# 5-MCU.net
KiCad netlist of a schematic drawn in Altium Designer
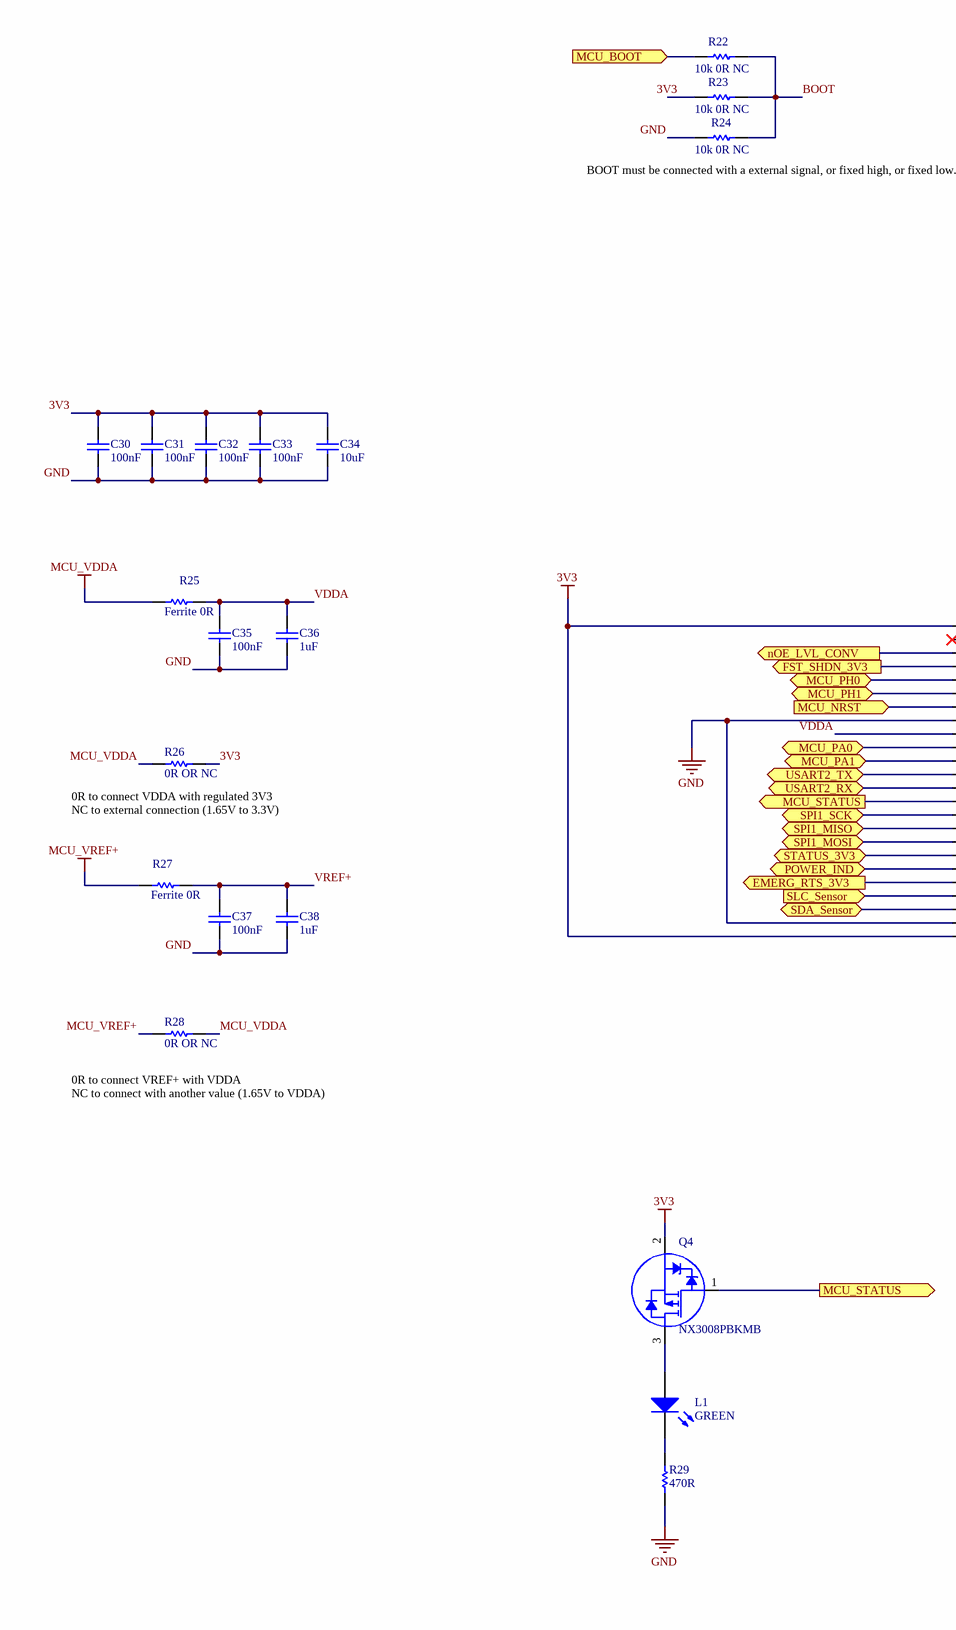
[diagram p0: 5-MCU.SchDoc, left]
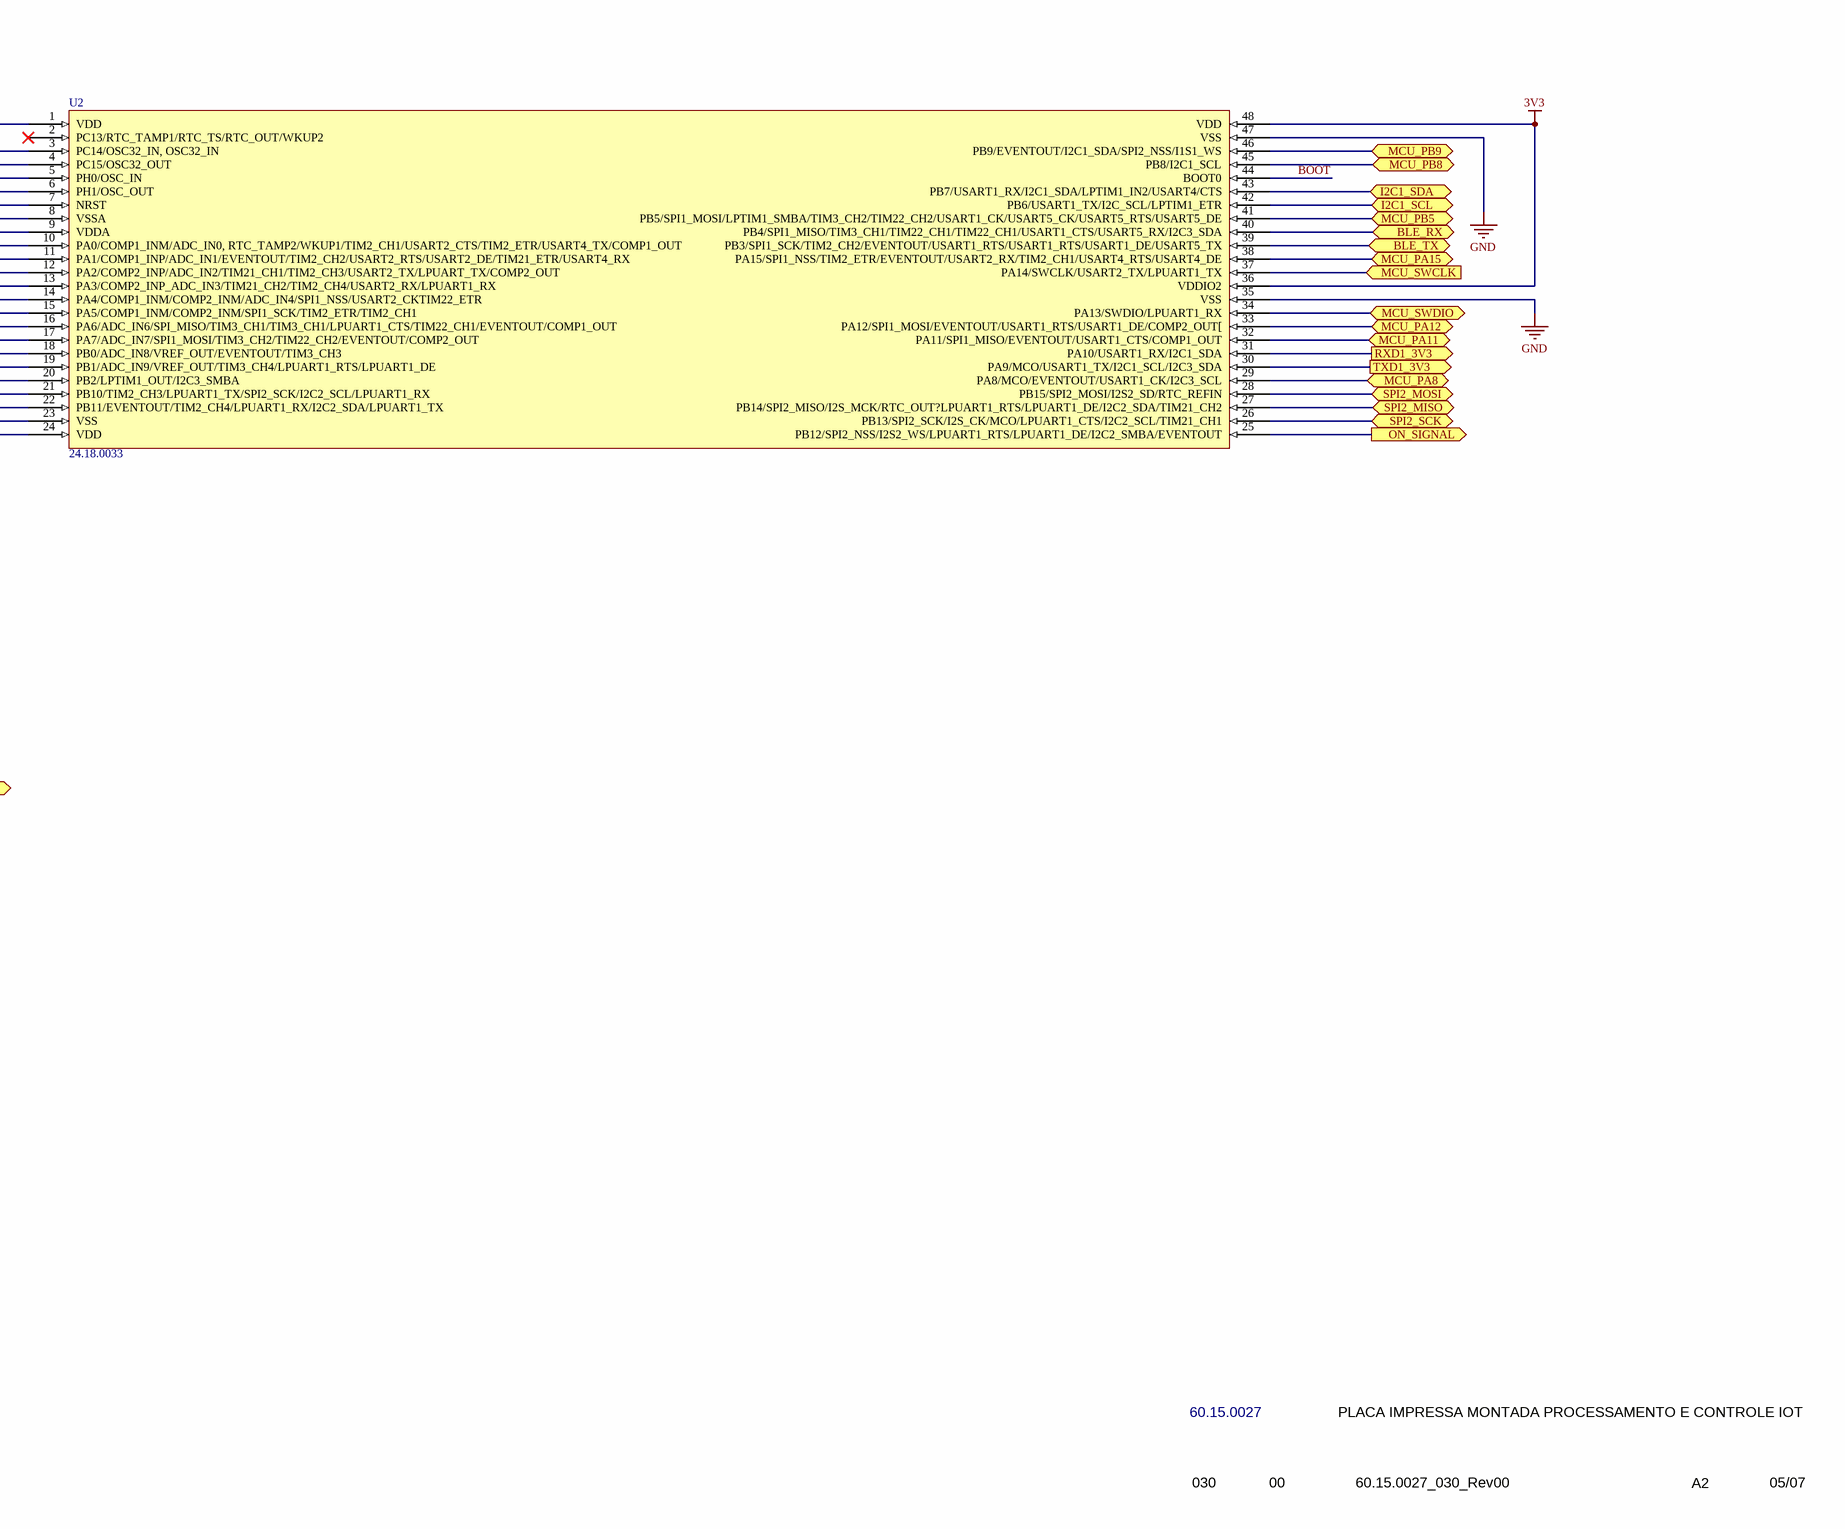
[diagram p1: 5-MCU.SchDoc, right]

(export (version "E")
  (design (tool "Eeschema 10.0.6"))
  (components
    (comp (ref "C30")
      (value "16.23.0803")
      (footprint "16.23.0803")
      (description "CAPACITOR CERAMICO 100nF 16V 10%% X5R SMD 0201")
      (fields (field (name "ALTIUM_UNNAMED_1") "100nF"))
      (libsource (lib "OMNI-CAPACITORES") (part "16.23.0803"))
    )
    (comp (ref "C31")
      (value "16.23.0803")
      (footprint "16.23.0803")
      (description "CAPACITOR CERAMICO 100nF 16V 10%% X5R SMD 0201")
      (fields (field (name "ALTIUM_UNNAMED_1") "100nF"))
      (libsource (lib "OMNI-CAPACITORES") (part "16.23.0803"))
    )
    (comp (ref "C32")
      (value "16.23.0803")
      (footprint "16.23.0803")
      (description "CAPACITOR CERAMICO 100nF 16V 10%% X5R SMD 0201")
      (fields (field (name "ALTIUM_UNNAMED_1") "100nF"))
      (libsource (lib "OMNI-CAPACITORES") (part "16.23.0803"))
    )
    (comp (ref "C33")
      (value "16.23.0803")
      (footprint "16.23.0803")
      (description "CAPACITOR CERAMICO 100nF 16V 10%% X5R SMD 0201")
      (fields (field (name "ALTIUM_UNNAMED_1") "100nF"))
      (libsource (lib "OMNI-CAPACITORES") (part "16.23.0803"))
    )
    (comp (ref "C34")
      (value "10uF")
      (footprint "16.23.0805")
      (description "CAPACITOR CERAMICO MULTICAMADAS 10uF 10V X5R 10% SMD 0603")
      (fields (field (name "Comment") "16.23.0805"))
      (libsource (lib "OMNI-CAPACITORES") (part "16.23.0805"))
    )
    (comp (ref "C35")
      (value "16.23.0803")
      (footprint "16.23.0803")
      (description "CAPACITOR CERAMICO 100nF 16V 10%% X5R SMD 0201")
      (fields (field (name "ALTIUM_UNNAMED_1") "100nF"))
      (libsource (lib "OMNI-CAPACITORES") (part "16.23.0803"))
    )
    (comp (ref "C36")
      (value "1uF")
      (footprint "16.23.0806")
      (description "CAPACITOR CERAMICO MULTICAMADAS 1uF 10V X5R 20% SMD 0201")
      (fields (field (name "Comment") "16.23.0806"))
      (libsource (lib "OMNI-CAPACITORES") (part "16.23.0806"))
    )
    (comp (ref "C37")
      (value "16.23.0803")
      (footprint "16.23.0803")
      (description "CAPACITOR CERAMICO 100nF 16V 10%% X5R SMD 0201")
      (fields (field (name "ALTIUM_UNNAMED_1") "100nF"))
      (libsource (lib "OMNI-CAPACITORES") (part "16.23.0803"))
    )
    (comp (ref "C38")
      (value "1uF")
      (footprint "16.23.0806")
      (description "CAPACITOR CERAMICO MULTICAMADAS 1uF 10V X5R 20% SMD 0201")
      (fields (field (name "Comment") "16.23.0806"))
      (libsource (lib "OMNI-CAPACITORES") (part "16.23.0806"))
    )
    (comp (ref "L1")
      (value "32.17.0036")
      (footprint "32.17.0036")
      (description "LED VERDE 0603 SMD")
      (fields (field (name "ALTIUM_UNNAMED_1") "GREEN"))
      (libsource (lib "OMNI-DIODOS_LED´s_DISPLAYS") (part "32.17.0036"))
    )
    (comp (ref "Q4")
      (value "72.19.0071")
      (footprint "72.19.0071")
      (description "MOSFET CANAL P SMD 30V 230mA SOT883B")
      (fields (field (name "ALTIUM_UNNAMED_1") "NX3008PBKMB"))
      (libsource (lib "OMNI-TRANSISTORES") (part "72.19.0071"))
    )
    (comp (ref "R22")
      (value "10k 0R NC")
      (footprint "66.21.1646")
      (description "RESISTOR THICK FILM 10k OHMS 25V 0.05W 1% SMD 0201")
      (fields (field (name "Comment") "66.21.1646"))
      (libsource (lib "OMNI-RESISTORES") (part "66.21.1646"))
    )
    (comp (ref "R23")
      (value "10k 0R NC")
      (footprint "66.21.1646")
      (description "RESISTOR THICK FILM 10k OHMS 25V 0.05W 1% SMD 0201")
      (fields (field (name "Comment") "66.21.1646"))
      (libsource (lib "OMNI-RESISTORES") (part "66.21.1646"))
    )
    (comp (ref "R24")
      (value "10k 0R NC")
      (footprint "66.21.1646")
      (description "RESISTOR THICK FILM 10k OHMS 25V 0.05W 1% SMD 0201")
      (fields (field (name "Comment") "66.21.1646"))
      (libsource (lib "OMNI-RESISTORES") (part "66.21.1646"))
    )
    (comp (ref "R25")
      (value "Ferrite 0R")
      (footprint "66.24.1337")
      (description "RESISTOR THICK FILM 0,1W 0 OHMS SMD 0603")
      (fields (field (name "Comment") "66.24.1337"))
      (libsource (lib "OMNI-RESISTORES") (part "66.24.1337"))
    )
    (comp (ref "R26")
      (value "0R OR NC")
      (footprint "66.24.1337")
      (description "RESISTOR THICK FILM 0,1W 0 OHMS SMD 0603")
      (fields (field (name "Comment") "66.24.1337"))
      (libsource (lib "OMNI-RESISTORES") (part "66.24.1337"))
    )
    (comp (ref "R27")
      (value "Ferrite 0R")
      (footprint "66.24.1337")
      (description "RESISTOR THICK FILM 0,1W 0 OHMS SMD 0603")
      (fields (field (name "Comment") "66.24.1337"))
      (libsource (lib "OMNI-RESISTORES") (part "66.24.1337"))
    )
    (comp (ref "R28")
      (value "0R OR NC")
      (footprint "66.24.1337")
      (description "RESISTOR THICK FILM 0,1W 0 OHMS SMD 0603")
      (fields (field (name "Comment") "66.24.1337"))
      (libsource (lib "OMNI-RESISTORES") (part "66.24.1337"))
    )
    (comp (ref "R29")
      (value "470R")
      (footprint "66.33.4700")
      (description "RES MET 0,125W 470 OHMS 5% SMD 0805")
      (fields (field (name "Comment") "66.33.4700"))
      (libsource (lib "OMNI-RESISTORES") (part "66.33.4700"))
    )
    (comp (ref "U2")
      (value "24.18.0033")
      (footprint "24.18.0033")
      (description "MICROCONTROLADOR 32BITS ARM 192KB FLASH 48 PINOS LQFP")
      (fields (field (name "PART NUMBER") "STM32L071CZTx"))
      (libsource (lib "OMNI-CI´S DIGITAIS") (part "24.18.0033"))
    )
  )
  (nets
    (net (code "1") (name "/BLE_RX") (class "Default")
      (node (ref "U2") (pin "40") (pinfunction "PB4/SPI1_MISO/TIM3_CH1/TIM22_CH1/TIM22_CH1/USART1_CTS/USART5_RX/I2C3_SDA_40") (pintype "input"))
    )
    (net (code "2") (name "/BLE_TX") (class "Default")
      (node (ref "U2") (pin "39") (pinfunction "PB3/SPI1_SCK/TIM2_CH2/EVENTOUT/USART1_RTS/USART1_RTS/USART1_DE/USART5_TX_39") (pintype "input"))
    )
    (net (code "3") (name "/BOOT") (class "Default")
      (node (ref "R22") (pin "2") (pinfunction "2_2") (pintype "passive"))
      (node (ref "R23") (pin "2") (pinfunction "2_2") (pintype "passive"))
      (node (ref "R24") (pin "2") (pinfunction "2_2") (pintype "passive"))
      (node (ref "U2") (pin "44") (pinfunction "BOOT0_44") (pintype "input"))
    )
    (net (code "4") (name "/EMERG_RTS_3V3") (class "Default")
      (node (ref "U2") (pin "20") (pinfunction "PB2/LPTIM1_OUT/I2C3_SMBA_20") (pintype "input"))
    )
    (net (code "5") (name "/FST_SHDN_3V3") (class "Default")
      (node (ref "U2") (pin "4") (pinfunction "PC15/OSC32_OUT_4") (pintype "input"))
    )
    (net (code "6") (name "/I2C1_SCL") (class "Default")
      (node (ref "U2") (pin "42") (pinfunction "PB6/USART1_TX/I2C_SCL/LPTIM1_ETR_42") (pintype "input"))
    )
    (net (code "7") (name "/I2C1_SDA") (class "Default")
      (node (ref "U2") (pin "43") (pinfunction "PB7/USART1_RX/I2C1_SDA/LPTIM1_IN2/USART4/CTS_43") (pintype "input"))
    )
    (net (code "8") (name "/MCU_BOOT") (class "Default")
      (node (ref "R22") (pin "1") (pinfunction "1_1") (pintype "passive"))
    )
    (net (code "9") (name "/MCU_NRST") (class "Default")
      (node (ref "U2") (pin "7") (pinfunction "NRST_7") (pintype "input"))
    )
    (net (code "10") (name "/MCU_PA0") (class "Default")
      (node (ref "U2") (pin "10") (pinfunction "PA0/COMP1_INM/ADC_IN0,_RTC_TAMP2/WKUP1/TIM2_CH1/USART2_CTS/TIM2_ETR/USART4_TX/COMP1_OUT_10") (pintype "input"))
    )
    (net (code "11") (name "/MCU_PA1") (class "Default")
      (node (ref "U2") (pin "11") (pinfunction "PA1/COMP1_INP/ADC_IN1/EVENTOUT/TIM2_CH2/USART2_RTS/USART2_DE/TIM21_ETR/USART4_RX_11") (pintype "input"))
    )
    (net (code "12") (name "/MCU_PA8") (class "Default")
      (node (ref "U2") (pin "29") (pinfunction "PA8/MCO/EVENTOUT/USART1_CK/I2C3_SCL_29") (pintype "input"))
    )
    (net (code "13") (name "/MCU_PA11") (class "Default")
      (node (ref "U2") (pin "32") (pinfunction "PA11/SPI1_MISO/EVENTOUT/USART1_CTS/COMP1_OUT_32") (pintype "input"))
    )
    (net (code "14") (name "/MCU_PA12") (class "Default")
      (node (ref "U2") (pin "33") (pinfunction "PA12/SPI1_MOSI/EVENTOUT/USART1_RTS/USART1_DE/COMP2_OUT[_33") (pintype "input"))
    )
    (net (code "15") (name "/MCU_PA15") (class "Default")
      (node (ref "U2") (pin "38") (pinfunction "PA15/SPI1_NSS/TIM2_ETR/EVENTOUT/USART2_RX/TIM2_CH1/USART4_RTS/USART4_DE_38") (pintype "input"))
    )
    (net (code "16") (name "/MCU_PB5") (class "Default")
      (node (ref "U2") (pin "41") (pinfunction "PB5/SPI1_MOSI/LPTIM1_SMBA/TIM3_CH2/TIM22_CH2/USART1_CK/USART5_CK/USART5_RTS/USART5_DE_41") (pintype "input"))
    )
    (net (code "17") (name "/MCU_PB8") (class "Default")
      (node (ref "U2") (pin "45") (pinfunction "PB8/I2C1_SCL_45") (pintype "input"))
    )
    (net (code "18") (name "/MCU_PB9") (class "Default")
      (node (ref "U2") (pin "46") (pinfunction "PB9/EVENTOUT/I2C1_SDA/SPI2_NSS/I1S1_WS_46") (pintype "input"))
    )
    (net (code "19") (name "/MCU_PH0") (class "Default")
      (node (ref "U2") (pin "5") (pinfunction "PH0/OSC_IN_5") (pintype "input"))
    )
    (net (code "20") (name "/MCU_PH1") (class "Default")
      (node (ref "U2") (pin "6") (pinfunction "PH1/OSC_OUT_6") (pintype "input"))
    )
    (net (code "21") (name "/MCU_STATUS") (class "Default")
      (node (ref "Q4") (pin "1") (pinfunction "G_1") (pintype "passive"))
      (node (ref "U2") (pin "14") (pinfunction "PA4/COMP1_INM/COMP2_INM/ADC_IN4/SPI1_NSS/USART2_CKTIM22_ETR_14") (pintype "input"))
    )
    (net (code "22") (name "/MCU_SWCLK") (class "Default")
      (node (ref "U2") (pin "37") (pinfunction "PA14/SWCLK/USART2_TX/LPUART1_TX_37") (pintype "input"))
    )
    (net (code "23") (name "/MCU_SWDIO") (class "Default")
      (node (ref "U2") (pin "34") (pinfunction "PA13/SWDIO/LPUART1_RX_34") (pintype "input"))
    )
    (net (code "24") (name "/ON_SIGNAL") (class "Default")
      (node (ref "U2") (pin "25") (pinfunction "PB12/SPI2_NSS/I2S2_WS/LPUART1_RTS/LPUART1_DE/I2C2_SMBA/EVENTOUT_25") (pintype "input"))
    )
    (net (code "25") (name "/POWER_IND") (class "Default")
      (node (ref "U2") (pin "19") (pinfunction "PB1/ADC_IN9/VREF_OUT/TIM3_CH4/LPUART1_RTS/LPUART1_DE_19") (pintype "input"))
    )
    (net (code "26") (name "/RXD1_3V3") (class "Default")
      (node (ref "U2") (pin "31") (pinfunction "PA10/USART1_RX/I2C1_SDA_31") (pintype "input"))
    )
    (net (code "27") (name "/SDA_Sensor") (class "Default")
      (node (ref "U2") (pin "22") (pinfunction "PB11/EVENTOUT/TIM2_CH4/LPUART1_RX/I2C2_SDA/LPUART1_TX_22") (pintype "input"))
    )
    (net (code "28") (name "/SLC_Sensor") (class "Default")
      (node (ref "U2") (pin "21") (pinfunction "PB10/TIM2_CH3/LPUART1_TX/SPI2_SCK/I2C2_SCL/LPUART1_RX_21") (pintype "input"))
    )
    (net (code "29") (name "/SPI1_MISO") (class "Default")
      (node (ref "U2") (pin "16") (pinfunction "PA6/ADC_IN6/SPI_MISO/TIM3_CH1/TIM3_CH1/LPUART1_CTS/TIM22_CH1/EVENTOUT/COMP1_OUT_16") (pintype "input"))
    )
    (net (code "30") (name "/SPI1_MOSI") (class "Default")
      (node (ref "U2") (pin "17") (pinfunction "PA7/ADC_IN7/SPI1_MOSI/TIM3_CH2/TIM22_CH2/EVENTOUT/COMP2_OUT_17") (pintype "input"))
    )
    (net (code "31") (name "/SPI1_SCK") (class "Default")
      (node (ref "U2") (pin "15") (pinfunction "PA5/COMP1_INM/COMP2_INM/SPI1_SCK/TIM2_ETR/TIM2_CH1_15") (pintype "input"))
    )
    (net (code "32") (name "/SPI2_MISO") (class "Default")
      (node (ref "U2") (pin "27") (pinfunction "PB14/SPI2_MISO/I2S_MCK/RTC_OUT?LPUART1_RTS/LPUART1_DE/I2C2_SDA/TIM21_CH2_27") (pintype "input"))
    )
    (net (code "33") (name "/SPI2_MOSI") (class "Default")
      (node (ref "U2") (pin "28") (pinfunction "PB15/SPI2_MOSI/I2S2_SD/RTC_REFIN_28") (pintype "input"))
    )
    (net (code "34") (name "/SPI2_SCK") (class "Default")
      (node (ref "U2") (pin "26") (pinfunction "PB13/SPI2_SCK/I2S_CK/MCO/LPUART1_CTS/I2C2_SCL/TIM21_CH1_26") (pintype "input"))
    )
    (net (code "35") (name "/STATUS_3V3") (class "Default")
      (node (ref "U2") (pin "18") (pinfunction "PB0/ADC_IN8/VREF_OUT/EVENTOUT/TIM3_CH3_18") (pintype "input"))
    )
    (net (code "36") (name "/TXD1_3V3") (class "Default")
      (node (ref "U2") (pin "30") (pinfunction "PA9/MCO/USART1_TX/I2C1_SCL/I2C3_SDA_30") (pintype "input"))
    )
    (net (code "37") (name "/USART2_RX") (class "Default")
      (node (ref "U2") (pin "13") (pinfunction "PA3/COMP2_INP_ADC_IN3/TIM21_CH2/TIM2_CH4/USART2_RX/LPUART1_RX_13") (pintype "input"))
    )
    (net (code "38") (name "/USART2_TX") (class "Default")
      (node (ref "U2") (pin "12") (pinfunction "PA2/COMP2_INP/ADC_IN2/TIM21_CH1/TIM2_CH3/USART2_TX/LPUART_TX/COMP2_OUT_12") (pintype "input"))
    )
    (net (code "39") (name "/VDDA") (class "Default")
      (node (ref "C35") (pin "2") (pinfunction "2_2") (pintype "passive"))
      (node (ref "C36") (pin "2") (pinfunction "2_2") (pintype "passive"))
      (node (ref "R25") (pin "2") (pinfunction "2_2") (pintype "passive"))
      (node (ref "U2") (pin "9") (pinfunction "VDDA_9") (pintype "input"))
    )
    (net (code "40") (name "/VREF+") (class "Default")
      (node (ref "C37") (pin "2") (pinfunction "2_2") (pintype "passive"))
      (node (ref "C38") (pin "2") (pinfunction "2_2") (pintype "passive"))
      (node (ref "R27") (pin "2") (pinfunction "2_2") (pintype "passive"))
    )
    (net (code "41") (name "/nOE_LVL_CONV") (class "Default")
      (node (ref "U2") (pin "3") (pinfunction "PC14/OSC32_IN,_OSC32_IN_3") (pintype "input"))
    )
    (net (code "42") (name "3V3") (class "Default")
      (node (ref "C30") (pin "2") (pinfunction "2_2") (pintype "passive"))
      (node (ref "C31") (pin "2") (pinfunction "2_2") (pintype "passive"))
      (node (ref "C32") (pin "2") (pinfunction "2_2") (pintype "passive"))
      (node (ref "C33") (pin "2") (pinfunction "2_2") (pintype "passive"))
      (node (ref "C34") (pin "2") (pinfunction "2_2") (pintype "passive"))
      (node (ref "Q4") (pin "2") (pinfunction "S_2") (pintype "passive"))
      (node (ref "R23") (pin "1") (pinfunction "1_1") (pintype "passive"))
      (node (ref "R26") (pin "2") (pinfunction "2_2") (pintype "passive"))
      (node (ref "U2") (pin "1") (pinfunction "VDD_1") (pintype "input"))
      (node (ref "U2") (pin "24") (pinfunction "VDD_24") (pintype "input"))
      (node (ref "U2") (pin "36") (pinfunction "VDDIO2_36") (pintype "input"))
      (node (ref "U2") (pin "48") (pinfunction "VDD_48") (pintype "input"))
    )
    (net (code "43") (name "GND") (class "Default")
      (node (ref "C30") (pin "1") (pinfunction "1_1") (pintype "passive"))
      (node (ref "C31") (pin "1") (pinfunction "1_1") (pintype "passive"))
      (node (ref "C32") (pin "1") (pinfunction "1_1") (pintype "passive"))
      (node (ref "C33") (pin "1") (pinfunction "1_1") (pintype "passive"))
      (node (ref "C34") (pin "1") (pinfunction "1_1") (pintype "passive"))
      (node (ref "C35") (pin "1") (pinfunction "1_1") (pintype "passive"))
      (node (ref "C36") (pin "1") (pinfunction "1_1") (pintype "passive"))
      (node (ref "C37") (pin "1") (pinfunction "1_1") (pintype "passive"))
      (node (ref "C38") (pin "1") (pinfunction "1_1") (pintype "passive"))
      (node (ref "R24") (pin "1") (pinfunction "1_1") (pintype "passive"))
      (node (ref "R29") (pin "1") (pinfunction "1_1") (pintype "passive"))
      (node (ref "U2") (pin "23") (pinfunction "VSS_23") (pintype "input"))
      (node (ref "U2") (pin "35") (pinfunction "VSS_35") (pintype "input"))
      (node (ref "U2") (pin "47") (pinfunction "VSS_47") (pintype "input"))
      (node (ref "U2") (pin "8") (pinfunction "VSSA_8") (pintype "input"))
    )
    (net (code "44") (name "MCU_VDDA") (class "Default")
      (node (ref "R25") (pin "1") (pinfunction "1_1") (pintype "passive"))
      (node (ref "R26") (pin "1") (pinfunction "1_1") (pintype "passive"))
      (node (ref "R28") (pin "2") (pinfunction "2_2") (pintype "passive"))
    )
    (net (code "45") (name "MCU_VREF+") (class "Default")
      (node (ref "R27") (pin "1") (pinfunction "1_1") (pintype "passive"))
      (node (ref "R28") (pin "1") (pinfunction "1_1") (pintype "passive"))
    )
    (net (code "46") (name "Net-(L1-PadK)") (class "Default")
      (node (ref "L1") (pin "K") (pinfunction "K_K") (pintype "passive"))
      (node (ref "R29") (pin "2") (pinfunction "2_2") (pintype "passive"))
    )
    (net (code "47") (name "Net-(Q4-D)") (class "Default")
      (node (ref "L1") (pin "A") (pinfunction "A_A") (pintype "passive"))
      (node (ref "Q4") (pin "3") (pinfunction "D_3") (pintype "passive"))
    )
    (net (code "48") (name "unconnected-(U2-PC13{slash}RTC_TAMP1{slash}RTC_TS{slash}RTC_OUT{slash}WKUP2-Pad2)") (class "Default")
      (node (ref "U2") (pin "2") (pinfunction "PC13/RTC_TAMP1/RTC_TS/RTC_OUT/WKUP2_2") (pintype "input+no_connect"))
    )
  )
)
